# ip_phone_b_miscellaneous.net
KiCad netlist of a schematic drawn in Altium Designer
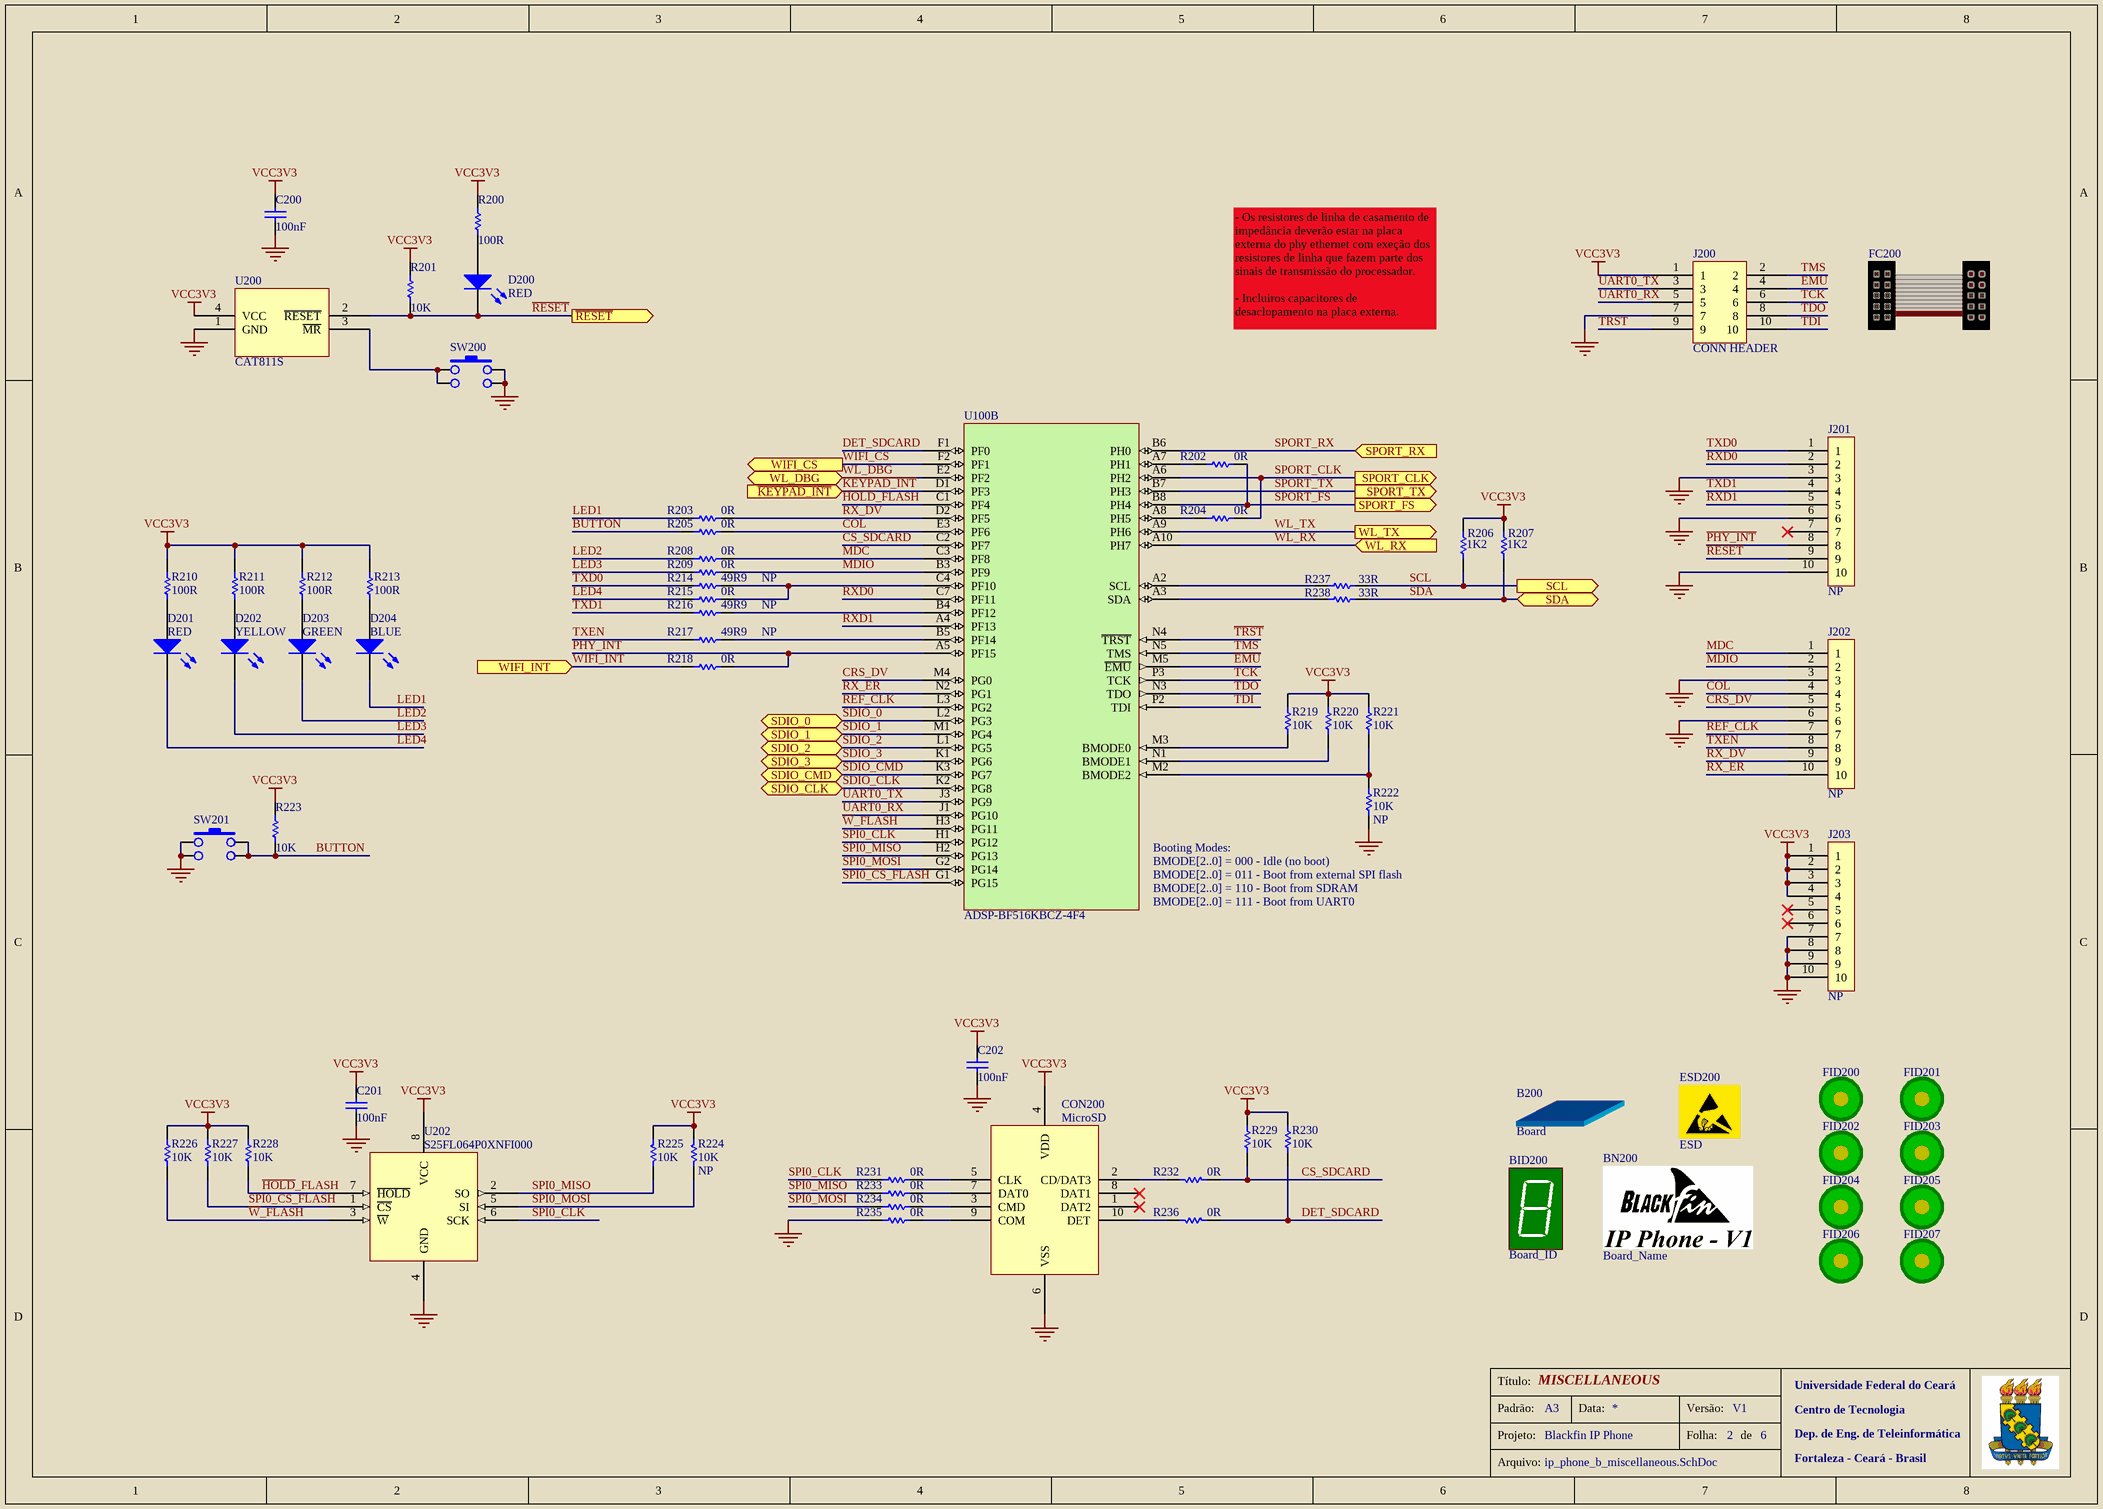
[diagram p0: ip_phone_b_miscellaneous.SchDoc]

(export (version "E")
  (design (tool "Eeschema 10.0.6"))
  (components
    (comp (ref "B200") (value "Board") (libsource (lib "ip_phone") (part "Board")))
    (comp (ref "BID200")
      (value "Board_ID")
      (footprint "ip_phone:BOARD_ID")
      (fields (field (name "EVENDORPART#") "NÃO SE APLICA"))
      (libsource (lib "ip_phone") (part "Board_ID"))
    )
    (comp (ref "BN200")
      (value "Board_Name")
      (footprint "ip_phone:LOGO")
      (fields (field (name "EVENDORPART#") "NÃO SE APLICA"))
      (libsource (lib "ip_phone") (part "Board_Name"))
    )
    (comp (ref "C200")
      (value "100nF")
      (footprint "ip_phone:CC1005-0402")
      (description "MLCC - SMD/SMT 0.1UF 16V 10% 0402")
      (fields (field (name "EVENDORPART#") "810-C1005X7R1C104K") (field (name "MANUFACTURER") "TDK"))
      (libsource (lib "ip_phone") (part "Capacitor"))
    )
    (comp (ref "C201")
      (value "100nF")
      (footprint "ip_phone:CC1005-0402")
      (description "MLCC - SMD/SMT 0.1UF 16V 10% 0402")
      (fields (field (name "EVENDORPART#") "810-C1005X7R1C104K") (field (name "MANUFACTURER") "TDK"))
      (libsource (lib "ip_phone") (part "Capacitor"))
    )
    (comp (ref "C202")
      (value "100nF")
      (footprint "ip_phone:CC1005-0402")
      (description "MLCC - SMD/SMT 0.1UF 16V 10% 0402")
      (fields (field (name "EVENDORPART#") "810-C1005X7R1C104K") (field (name "MANUFACTURER") "TDK"))
      (libsource (lib "ip_phone") (part "Capacitor"))
    )
    (comp (ref "CON200")
      (value "MicroSD")
      (footprint "ip_phone:MICRO_SD")
      (description "CONN MEMORY CARD SD SMD")
      (fields (field (name "MANUFACTURER") "AVX Corporation") (field (name "PART#") "045138008010890+"))
      (libsource (lib "ip_phone") (part "MicroSD"))
    )
    (comp (ref "D200")
      (value "RED")
      (footprint "ip_phone:LED_0603")
      (description "LED")
      (fields (field (name "PART#") "APT1608SURCK") (field (name "MANUFACTURER") "Kingbright"))
      (libsource (lib "ip_phone") (part "LED"))
    )
    (comp (ref "D201")
      (value "RED")
      (footprint "ip_phone:LED_0603")
      (description "LED")
      (fields (field (name "PART#") "APT1608SURCK") (field (name "MANUFACTURER") "Kingbright"))
      (libsource (lib "ip_phone") (part "LED"))
    )
    (comp (ref "D202")
      (value "YELLOW")
      (footprint "ip_phone:LED_0603")
      (description "LED")
      (fields (field (name "PART#") "APT1608SYCK") (field (name "MANUFACTURER") "Kingbright"))
      (libsource (lib "ip_phone") (part "LED"))
    )
    (comp (ref "D203")
      (value "GREEN")
      (footprint "ip_phone:LED_0603")
      (description "LED")
      (fields (field (name "PART#") "APT1608CGCK") (field (name "MANUFACTURER") "Kingbright"))
      (libsource (lib "ip_phone") (part "LED"))
    )
    (comp (ref "D204")
      (value "BLUE")
      (footprint "ip_phone:LED_0603")
      (description "LED")
      (fields (field (name "PART#") "EL-19-21/BHC-AN1P2/3T") (field (name "MANUFACTURER") "Everlight"))
      (libsource (lib "ip_phone") (part "LED"))
    )
    (comp (ref "ESD200")
      (value "ESD")
      (footprint "ip_phone:ESD")
      (fields (field (name "EVENDORPART#") "NÃO SE APLICA"))
      (libsource (lib "ip_phone") (part "ESD"))
    )
    (comp (ref "FC200")
      (value "Flat Cable")
      (fields (field (name "EVENDORPART#") "SAM8218-ND") (field (name "MANUFACTURER") "Samtec"))
      (libsource (lib "ip_phone") (part "Flat_Cable"))
    )
    (comp (ref "FID200")
      (value "Fiducial")
      (footprint "ip_phone:Fiducial")
      (fields (field (name "EVENDORPART#") "NÃO SE APLICA"))
      (libsource (lib "ip_phone") (part "Fiducial"))
    )
    (comp (ref "FID201")
      (value "Fiducial")
      (footprint "ip_phone:Fiducial")
      (fields (field (name "EVENDORPART#") "NÃO SE APLICA"))
      (libsource (lib "ip_phone") (part "Fiducial"))
    )
    (comp (ref "FID202")
      (value "Fiducial")
      (footprint "ip_phone:Fiducial")
      (fields (field (name "EVENDORPART#") "NÃO SE APLICA"))
      (libsource (lib "ip_phone") (part "Fiducial"))
    )
    (comp (ref "FID203")
      (value "Fiducial")
      (footprint "ip_phone:Fiducial")
      (fields (field (name "EVENDORPART#") "NÃO SE APLICA"))
      (libsource (lib "ip_phone") (part "Fiducial"))
    )
    (comp (ref "FID204")
      (value "Fiducial")
      (footprint "ip_phone:Fiducial")
      (fields (field (name "EVENDORPART#") "NÃO SE APLICA"))
      (libsource (lib "ip_phone") (part "Fiducial"))
    )
    (comp (ref "FID205")
      (value "Fiducial")
      (footprint "ip_phone:Fiducial")
      (fields (field (name "EVENDORPART#") "NÃO SE APLICA"))
      (libsource (lib "ip_phone") (part "Fiducial"))
    )
    (comp (ref "FID206")
      (value "Fiducial")
      (footprint "ip_phone:Fiducial")
      (fields (field (name "EVENDORPART#") "NÃO SE APLICA"))
      (libsource (lib "ip_phone") (part "Fiducial"))
    )
    (comp (ref "FID207")
      (value "Fiducial")
      (footprint "ip_phone:Fiducial")
      (fields (field (name "EVENDORPART#") "NÃO SE APLICA"))
      (libsource (lib "ip_phone") (part "Fiducial"))
    )
    (comp (ref "J200")
      (value "CONN HEADER")
      (footprint "ip_phone:CON_JTAG")
      (description "CONN HEADER .050\" 5x2")
      (fields (field (name "EVENDORPART#") "S9012E-05-ND") (field (name "MANUFACTURER") "Sullins"))
      (libsource (lib "ip_phone") (part "Conector JTAG"))
    )
    (comp (ref "J201")
      (value "CONN HEADER")
      (footprint "ip_phone:CONECTOR_10_PIN")
      (description "CONN HEADER .050\" 10POS PCB GOLD")
      (fields
        (field (name "EVENDORPART#") "S9014E-10-ND")
        (field (name "MANUFACTURER") "Sullins Connector Solutions")
        (field (name "NP") "NP")
      )
      (libsource (lib "ip_phone") (part "Conector 10pin"))
    )
    (comp (ref "J202")
      (value "CONN HEADER")
      (footprint "ip_phone:CONECTOR_10_PIN")
      (description "CONN HEADER .050\" 10POS PCB GOLD")
      (fields
        (field (name "EVENDORPART#") "S9014E-10-ND")
        (field (name "MANUFACTURER") "Sullins Connector Solutions")
        (field (name "NP") "NP")
      )
      (libsource (lib "ip_phone") (part "Conector 10pin"))
    )
    (comp (ref "J203")
      (value "CONN HEADER")
      (footprint "ip_phone:CONECTOR_10_PIN")
      (description "CONN HEADER .050\" 10POS PCB GOLD")
      (fields
        (field (name "EVENDORPART#") "S9014E-10-ND")
        (field (name "MANUFACTURER") "Sullins Connector Solutions")
        (field (name "NP") "NP")
      )
      (libsource (lib "ip_phone") (part "Conector 10pin"))
    )
    (comp (ref "R200")
      (value "100R")
      (footprint "ip_phone:CR1608-0603")
      (description "Thick Film Resistors 1/16WATT 100R 0402")
      (fields (field (name "EVENDORPART#") "652-CR0603-JW-101GLF") (field (name "MANUFACTURER") "Bourns"))
      (libsource (lib "ip_phone") (part "Resistor"))
    )
    (comp (ref "R201")
      (value "10K")
      (footprint "ip_phone:CR1005-0402")
      (description "Thick Film Resistors SMD 0402 10K 5%  1/16 W")
      (fields (field (name "EVENDORPART#") "311-10KJRCT-ND") (field (name "MANUFACTURER") "Yageo"))
      (libsource (lib "ip_phone") (part "Resistor"))
    )
    (comp (ref "R202")
      (value "0R")
      (footprint "ip_phone:CR1005-0402")
      (description "Thick Film Resistors 0402 1/16W Jumper")
      (fields
        (field (name "EVENDORPART#") "667-ERJ-2GE0R00X")
        (field (name "MANUFACTURER") "Panasonic Electronic Components")
      )
      (libsource (lib "ip_phone") (part "Resistor"))
    )
    (comp (ref "R203")
      (value "0R")
      (footprint "ip_phone:CR1005-0402")
      (description "Thick Film Resistors 0402 1/16W Jumper")
      (fields
        (field (name "EVENDORPART#") "667-ERJ-2GE0R00X")
        (field (name "MANUFACTURER") "Panasonic Electronic Components")
      )
      (libsource (lib "ip_phone") (part "Resistor"))
    )
    (comp (ref "R204")
      (value "0R")
      (footprint "ip_phone:CR1005-0402")
      (description "Thick Film Resistors 0402 1/16W Jumper")
      (fields
        (field (name "EVENDORPART#") "667-ERJ-2GE0R00X")
        (field (name "MANUFACTURER") "Panasonic Electronic Components")
      )
      (libsource (lib "ip_phone") (part "Resistor"))
    )
    (comp (ref "R205")
      (value "0R")
      (footprint "ip_phone:CR1005-0402")
      (description "Thick Film Resistors 0402 1/16W Jumper")
      (fields
        (field (name "EVENDORPART#") "667-ERJ-2GE0R00X")
        (field (name "MANUFACTURER") "Panasonic Electronic Components")
      )
      (libsource (lib "ip_phone") (part "Resistor"))
    )
    (comp (ref "R206")
      (value "1K2")
      (footprint "ip_phone:CR1005-0402")
      (description "Thick Film Resistors SMD 0402 1K2 5%  1/16 W")
      (fields (field (name "EVENDORPART#") "311-1.2KJRCT-ND") (field (name "MANUFACTURER") "Yageo"))
      (libsource (lib "ip_phone") (part "Resistor"))
    )
    (comp (ref "R207")
      (value "1K2")
      (footprint "ip_phone:CR1005-0402")
      (description "Thick Film Resistors SMD 0402 1K2 5%  1/16 W")
      (fields (field (name "EVENDORPART#") "311-1.2KJRCT-ND") (field (name "MANUFACTURER") "Yageo"))
      (libsource (lib "ip_phone") (part "Resistor"))
    )
    (comp (ref "R208")
      (value "0R")
      (footprint "ip_phone:CR1005-0402")
      (description "Thick Film Resistors 0402 1/16W Jumper")
      (fields
        (field (name "EVENDORPART#") "667-ERJ-2GE0R00X")
        (field (name "MANUFACTURER") "Panasonic Electronic Components")
      )
      (libsource (lib "ip_phone") (part "Resistor"))
    )
    (comp (ref "R209")
      (value "0R")
      (footprint "ip_phone:CR1005-0402")
      (description "Thick Film Resistors 0402 1/16W Jumper")
      (fields
        (field (name "EVENDORPART#") "667-ERJ-2GE0R00X")
        (field (name "MANUFACTURER") "Panasonic Electronic Components")
      )
      (libsource (lib "ip_phone") (part "Resistor"))
    )
    (comp (ref "R210")
      (value "100R")
      (footprint "ip_phone:CR1608-0603")
      (description "Thick Film Resistors 1/16WATT 100R 0402")
      (fields (field (name "EVENDORPART#") "652-CR0603-JW-101GLF") (field (name "MANUFACTURER") "Bourns"))
      (libsource (lib "ip_phone") (part "Resistor"))
    )
    (comp (ref "R211")
      (value "100R")
      (footprint "ip_phone:CR1608-0603")
      (description "Thick Film Resistors 1/16WATT 100R 0402")
      (fields (field (name "EVENDORPART#") "652-CR0603-JW-101GLF") (field (name "MANUFACTURER") "Bourns"))
      (libsource (lib "ip_phone") (part "Resistor"))
    )
    (comp (ref "R212")
      (value "100R")
      (footprint "ip_phone:CR1608-0603")
      (description "Thick Film Resistors 1/16WATT 100R 0402")
      (fields (field (name "EVENDORPART#") "652-CR0603-JW-101GLF") (field (name "MANUFACTURER") "Bourns"))
      (libsource (lib "ip_phone") (part "Resistor"))
    )
    (comp (ref "R213")
      (value "100R")
      (footprint "ip_phone:CR1608-0603")
      (description "Thick Film Resistors 1/16WATT 100R 0402")
      (fields (field (name "EVENDORPART#") "652-CR0603-JW-101GLF") (field (name "MANUFACTURER") "Bourns"))
      (libsource (lib "ip_phone") (part "Resistor"))
    )
    (comp (ref "R214")
      (value "49R9")
      (footprint "ip_phone:CR1005-0402_NP")
      (description "Thick Film Resistors - SMD 1/16watt 49.9ohms 1% 0402")
      (fields
        (field (name "EVENDORPART#") "71-CRCW0402-49.9-E3")
        (field (name "MANUFACTURER") "Vishay/Dale")
        (field (name "NP") "NP")
      )
      (libsource (lib "ip_phone") (part "Resistor"))
    )
    (comp (ref "R215")
      (value "0R")
      (footprint "ip_phone:CR1005-0402")
      (description "Thick Film Resistors 0402 1/16W Jumper")
      (fields
        (field (name "EVENDORPART#") "667-ERJ-2GE0R00X")
        (field (name "MANUFACTURER") "Panasonic Electronic Components")
      )
      (libsource (lib "ip_phone") (part "Resistor"))
    )
    (comp (ref "R216")
      (value "49R9")
      (footprint "ip_phone:CR1005-0402_NP")
      (description "Thick Film Resistors - SMD 1/16watt 49.9ohms 1% 0402")
      (fields
        (field (name "EVENDORPART#") "71-CRCW0402-49.9-E3")
        (field (name "MANUFACTURER") "Vishay/Dale")
        (field (name "NP") "NP")
      )
      (libsource (lib "ip_phone") (part "Resistor"))
    )
    (comp (ref "R217")
      (value "49R9")
      (footprint "ip_phone:CR1005-0402_NP")
      (description "Thick Film Resistors - SMD 1/16watt 49.9ohms 1% 0402")
      (fields
        (field (name "EVENDORPART#") "71-CRCW0402-49.9-E3")
        (field (name "MANUFACTURER") "Vishay/Dale")
        (field (name "NP") "NP")
      )
      (libsource (lib "ip_phone") (part "Resistor"))
    )
    (comp (ref "R218")
      (value "0R")
      (footprint "ip_phone:CR1005-0402")
      (description "Thick Film Resistors 0402 1/16W Jumper")
      (fields
        (field (name "EVENDORPART#") "667-ERJ-2GE0R00X")
        (field (name "MANUFACTURER") "Panasonic Electronic Components")
      )
      (libsource (lib "ip_phone") (part "Resistor"))
    )
    (comp (ref "R219")
      (value "10K")
      (footprint "ip_phone:CR1005-0402")
      (description "Thick Film Resistors SMD 0402 10K 5%  1/16 W")
      (fields (field (name "EVENDORPART#") "311-10KJRCT-ND") (field (name "MANUFACTURER") "Yageo"))
      (libsource (lib "ip_phone") (part "Resistor"))
    )
    (comp (ref "R220")
      (value "10K")
      (footprint "ip_phone:CR1005-0402")
      (description "Thick Film Resistors SMD 0402 10K 5%  1/16 W")
      (fields (field (name "EVENDORPART#") "311-10KJRCT-ND") (field (name "MANUFACTURER") "Yageo"))
      (libsource (lib "ip_phone") (part "Resistor"))
    )
    (comp (ref "R221")
      (value "10K")
      (footprint "ip_phone:CR1005-0402")
      (description "Thick Film Resistors SMD 0402 10K 5%  1/16 W")
      (fields (field (name "EVENDORPART#") "311-10KJRCT-ND") (field (name "MANUFACTURER") "Yageo"))
      (libsource (lib "ip_phone") (part "Resistor"))
    )
    (comp (ref "R222")
      (value "10K")
      (footprint "ip_phone:CR1005-0402_NP")
      (description "Thick Film Resistors SMD 0402 10K 5%  1/16 W")
      (fields
        (field (name "EVENDORPART#") "311-10KJRCT-ND")
        (field (name "MANUFACTURER") "Yageo")
        (field (name "NP") "NP")
      )
      (libsource (lib "ip_phone") (part "Resistor"))
    )
    (comp (ref "R223")
      (value "10K")
      (footprint "ip_phone:CR1005-0402")
      (description "Thick Film Resistors SMD 0402 10K 5%  1/16 W")
      (fields (field (name "EVENDORPART#") "311-10KJRCT-ND") (field (name "MANUFACTURER") "Yageo"))
      (libsource (lib "ip_phone") (part "Resistor"))
    )
    (comp (ref "R224")
      (value "10K")
      (footprint "ip_phone:CR1005-0402_NP")
      (description "Thick Film Resistors SMD 0402 10K 5%  1/16 W")
      (fields
        (field (name "EVENDORPART#") "311-10KJRCT-ND")
        (field (name "MANUFACTURER") "Yageo")
        (field (name "NP") "NP")
      )
      (libsource (lib "ip_phone") (part "Resistor"))
    )
    (comp (ref "R225")
      (value "10K")
      (footprint "ip_phone:CR1005-0402")
      (description "Thick Film Resistors SMD 0402 10K 5%  1/16 W")
      (fields (field (name "EVENDORPART#") "311-10KJRCT-ND") (field (name "MANUFACTURER") "Yageo"))
      (libsource (lib "ip_phone") (part "Resistor"))
    )
    (comp (ref "R226")
      (value "10K")
      (footprint "ip_phone:CR1005-0402")
      (description "Thick Film Resistors SMD 0402 10K 5%  1/16 W")
      (fields (field (name "EVENDORPART#") "311-10KJRCT-ND") (field (name "MANUFACTURER") "Yageo"))
      (libsource (lib "ip_phone") (part "Resistor"))
    )
    (comp (ref "R227")
      (value "10K")
      (footprint "ip_phone:CR1005-0402")
      (description "Thick Film Resistors SMD 0402 10K 5%  1/16 W")
      (fields (field (name "EVENDORPART#") "311-10KJRCT-ND") (field (name "MANUFACTURER") "Yageo"))
      (libsource (lib "ip_phone") (part "Resistor"))
    )
    (comp (ref "R228")
      (value "10K")
      (footprint "ip_phone:CR1005-0402")
      (description "Thick Film Resistors SMD 0402 10K 5%  1/16 W")
      (fields (field (name "EVENDORPART#") "311-10KJRCT-ND") (field (name "MANUFACTURER") "Yageo"))
      (libsource (lib "ip_phone") (part "Resistor"))
    )
    (comp (ref "R229")
      (value "10K")
      (footprint "ip_phone:CR1005-0402")
      (description "Thick Film Resistors SMD 0402 10K 5%  1/16 W")
      (fields (field (name "EVENDORPART#") "311-10KJRCT-ND") (field (name "MANUFACTURER") "Yageo"))
      (libsource (lib "ip_phone") (part "Resistor"))
    )
    (comp (ref "R230")
      (value "10K")
      (footprint "ip_phone:CR1005-0402")
      (description "Thick Film Resistors SMD 0402 10K 5%  1/16 W")
      (fields (field (name "EVENDORPART#") "311-10KJRCT-ND") (field (name "MANUFACTURER") "Yageo"))
      (libsource (lib "ip_phone") (part "Resistor"))
    )
    (comp (ref "R231")
      (value "0R")
      (footprint "ip_phone:CR1005-0402")
      (description "Thick Film Resistors 0402 1/16W Jumper")
      (fields
        (field (name "EVENDORPART#") "667-ERJ-2GE0R00X")
        (field (name "MANUFACTURER") "Panasonic Electronic Components")
      )
      (libsource (lib "ip_phone") (part "Resistor"))
    )
    (comp (ref "R232")
      (value "0R")
      (footprint "ip_phone:CR1005-0402")
      (description "Thick Film Resistors 0402 1/16W Jumper")
      (fields
        (field (name "EVENDORPART#") "667-ERJ-2GE0R00X")
        (field (name "MANUFACTURER") "Panasonic Electronic Components")
      )
      (libsource (lib "ip_phone") (part "Resistor"))
    )
    (comp (ref "R233")
      (value "0R")
      (footprint "ip_phone:CR1005-0402")
      (description "Thick Film Resistors 0402 1/16W Jumper")
      (fields
        (field (name "EVENDORPART#") "667-ERJ-2GE0R00X")
        (field (name "MANUFACTURER") "Panasonic Electronic Components")
      )
      (libsource (lib "ip_phone") (part "Resistor"))
    )
    (comp (ref "R234")
      (value "0R")
      (footprint "ip_phone:CR1005-0402")
      (description "Thick Film Resistors 0402 1/16W Jumper")
      (fields
        (field (name "EVENDORPART#") "667-ERJ-2GE0R00X")
        (field (name "MANUFACTURER") "Panasonic Electronic Components")
      )
      (libsource (lib "ip_phone") (part "Resistor"))
    )
    (comp (ref "R235")
      (value "0R")
      (footprint "ip_phone:CR1005-0402")
      (description "Thick Film Resistors 0402 1/16W Jumper")
      (fields
        (field (name "EVENDORPART#") "667-ERJ-2GE0R00X")
        (field (name "MANUFACTURER") "Panasonic Electronic Components")
      )
      (libsource (lib "ip_phone") (part "Resistor"))
    )
    (comp (ref "R236")
      (value "0R")
      (footprint "ip_phone:CR1005-0402")
      (description "Thick Film Resistors 0402 1/16W Jumper")
      (fields
        (field (name "EVENDORPART#") "667-ERJ-2GE0R00X")
        (field (name "MANUFACTURER") "Panasonic Electronic Components")
      )
      (libsource (lib "ip_phone") (part "Resistor"))
    )
    (comp (ref "R237")
      (value "33R")
      (footprint "ip_phone:CR1005-0402")
      (description "Thick Film Resistors SMD 0402 33R 5%  1/16 W")
      (fields (field (name "EVENDORPART#") "311-33JRCT-ND") (field (name "MANUFACTURER") "Yageo"))
      (libsource (lib "ip_phone") (part "Resistor"))
    )
    (comp (ref "R238")
      (value "33R")
      (footprint "ip_phone:CR1005-0402")
      (description "Thick Film Resistors SMD 0402 33R 5%  1/16 W")
      (fields (field (name "EVENDORPART#") "311-33JRCT-ND") (field (name "MANUFACTURER") "Yageo"))
      (libsource (lib "ip_phone") (part "Resistor"))
    )
    (comp (ref "SW200")
      (value "SW")
      (footprint "ip_phone:PUSH-PTS525")
      (description "Switch tact, SMT, SPST, 160gf, 5.25 mm L x 5.25 mm W x 1.5 mm H")
      (fields (field (name "MANUFACTURER") "C&K Components") (field (name "PART#") "PTS525SM10SMTR LFS"))
      (libsource (lib "ip_phone") (part "SWITCH_PUSH_NA_SMD"))
    )
    (comp (ref "SW201")
      (value "SW")
      (footprint "ip_phone:PUSH-PTS525")
      (description "Switch tact, SMT, SPST, 160gf, 5.25 mm L x 5.25 mm W x 1.5 mm H")
      (fields (field (name "MANUFACTURER") "C&K Components") (field (name "PART#") "PTS525SM10SMTR LFS"))
      (libsource (lib "ip_phone") (part "SWITCH_PUSH_NA_SMD"))
    )
    (comp (ref "U100")
      (value "ADSP-BF516KBCZ-4F4")
      (footprint "ip_phone:BGA168")
      (description "Low Power Blackfin with Advanced Embedded Connectivity")
      (fields (field (name "MANUFACTURER") "Analog Device"))
      (libsource (lib "ip_phone") (part "ADSP-BF516KBCZ-4F4"))
    )
    (comp (ref "U200")
      (value "CAT811S")
      (footprint "ip_phone:SOT-143")
      (description "IC Supervisor MPU 2.93V  SOT-143")
      (fields (field (name "PART#") "CAT811STBI-GT3") (field (name "MANUFACTURER") "ON Semiconductor"))
      (libsource (lib "ip_phone") (part "CAT811S"))
    )
    (comp (ref "U202")
      (value "S25FL064P0XNFI000")
      (footprint "ip_phone:WSON8")
      (description "Flash Mem Serial-SPI 3V/3.3V 64M-Bit 64M x 1 8ns 8-Pin WSON Tray")
      (fields (field (name "MANUFACTURER") "Spansion"))
      (libsource (lib "ip_phone") (part "S25FL064P0XNFI000"))
    )
  )
  (nets
    (net (code "1") (name "/BUTTON") (class "Default")
      (node (ref "R205") (pin "1") (pinfunction "1_1") (pintype "passive"))
      (node (ref "R223") (pin "1") (pinfunction "1_1") (pintype "passive"))
      (node (ref "SW201") (pin "3") (pinfunction "3_3") (pintype "passive"))
      (node (ref "SW201") (pin "4") (pinfunction "4_4") (pintype "passive"))
    )
    (net (code "2") (name "/COL") (class "Default")
      (node (ref "J202") (pin "4") (pinfunction "4_4") (pintype "passive"))
      (node (ref "R205") (pin "2") (pinfunction "2_2") (pintype "passive"))
      (node (ref "U100") (pin "E3") (pinfunction "PF6_E3") (pintype "bidirectional"))
    )
    (net (code "3") (name "/CRS_DV") (class "Default")
      (node (ref "J202") (pin "5") (pinfunction "5_5") (pintype "passive"))
      (node (ref "U100") (pin "M4") (pinfunction "PG0_M4") (pintype "bidirectional"))
    )
    (net (code "4") (name "/CS_SDCARD") (class "Default")
      (node (ref "R229") (pin "1") (pinfunction "1_1") (pintype "passive"))
      (node (ref "R232") (pin "1") (pinfunction "1_1") (pintype "passive"))
      (node (ref "U100") (pin "C2") (pinfunction "PF7_C2") (pintype "bidirectional"))
    )
    (net (code "5") (name "/DET_SDCARD") (class "Default")
      (node (ref "R230") (pin "1") (pinfunction "1_1") (pintype "passive"))
      (node (ref "R236") (pin "1") (pinfunction "1_1") (pintype "passive"))
      (node (ref "U100") (pin "F1") (pinfunction "PF0_F1") (pintype "bidirectional"))
    )
    (net (code "6") (name "/LED1") (class "Default")
      (node (ref "D204") (pin "2") (pinfunction "K_2") (pintype "passive"))
      (node (ref "R203") (pin "1") (pinfunction "1_1") (pintype "passive"))
    )
    (net (code "7") (name "/LED2") (class "Default")
      (node (ref "D203") (pin "2") (pinfunction "K_2") (pintype "passive"))
      (node (ref "R208") (pin "1") (pinfunction "1_1") (pintype "passive"))
    )
    (net (code "8") (name "/LED3") (class "Default")
      (node (ref "D202") (pin "2") (pinfunction "K_2") (pintype "passive"))
      (node (ref "R209") (pin "1") (pinfunction "1_1") (pintype "passive"))
    )
    (net (code "9") (name "/LED4") (class "Default")
      (node (ref "D201") (pin "2") (pinfunction "K_2") (pintype "passive"))
      (node (ref "R215") (pin "1") (pinfunction "1_1") (pintype "passive"))
    )
    (net (code "10") (name "/MDC") (class "Default")
      (node (ref "J202") (pin "1") (pinfunction "1_1") (pintype "passive"))
      (node (ref "R208") (pin "2") (pinfunction "2_2") (pintype "passive"))
      (node (ref "U100") (pin "C3") (pinfunction "PF8_C3") (pintype "bidirectional"))
    )
    (net (code "11") (name "/MDIO") (class "Default")
      (node (ref "J202") (pin "2") (pinfunction "2_2") (pintype "passive"))
      (node (ref "R209") (pin "2") (pinfunction "2_2") (pintype "passive"))
      (node (ref "U100") (pin "B3") (pinfunction "PF9_B3") (pintype "bidirectional"))
    )
    (net (code "12") (name "/REF_CLK") (class "Default")
      (node (ref "J202") (pin "7") (pinfunction "7_7") (pintype "passive"))
      (node (ref "U100") (pin "L3") (pinfunction "PG2_L3") (pintype "bidirectional"))
    )
    (net (code "13") (name "/RXD0") (class "Default")
      (node (ref "J201") (pin "2") (pinfunction "2_2") (pintype "passive"))
      (node (ref "U100") (pin "C7") (pinfunction "PF11_C7") (pintype "bidirectional"))
    )
    (net (code "14") (name "/RXD1") (class "Default")
      (node (ref "J201") (pin "5") (pinfunction "5_5") (pintype "passive"))
      (node (ref "U100") (pin "A4") (pinfunction "PF13_A4") (pintype "bidirectional"))
    )
    (net (code "15") (name "/RX_DV") (class "Default")
      (node (ref "J202") (pin "9") (pinfunction "9_9") (pintype "passive"))
      (node (ref "R203") (pin "2") (pinfunction "2_2") (pintype "passive"))
      (node (ref "U100") (pin "D2") (pinfunction "PF5_D2") (pintype "bidirectional"))
    )
    (net (code "16") (name "/RX_ER") (class "Default")
      (node (ref "J202") (pin "10") (pinfunction "10_10") (pintype "passive"))
      (node (ref "U100") (pin "N2") (pinfunction "PG1_N2") (pintype "bidirectional"))
    )
    (net (code "17") (name "/SCL") (class "Default")
      (node (ref "R206") (pin "2") (pinfunction "2_2") (pintype "passive"))
      (node (ref "R237") (pin "2") (pinfunction "2_2") (pintype "passive"))
    )
    (net (code "18") (name "/SDA") (class "Default")
      (node (ref "R207") (pin "2") (pinfunction "2_2") (pintype "passive"))
      (node (ref "R238") (pin "2") (pinfunction "2_2") (pintype "passive"))
    )
    (net (code "19") (name "/SDIO_0") (class "Default")
      (node (ref "U100") (pin "L2") (pinfunction "PG3_L2") (pintype "bidirectional"))
    )
    (net (code "20") (name "/SDIO_1") (class "Default")
      (node (ref "U100") (pin "M1") (pinfunction "PG4_M1") (pintype "bidirectional"))
    )
    (net (code "21") (name "/SDIO_2") (class "Default")
      (node (ref "U100") (pin "L1") (pinfunction "PG5_L1") (pintype "bidirectional"))
    )
    (net (code "22") (name "/SDIO_3") (class "Default")
      (node (ref "U100") (pin "K1") (pinfunction "PG6_K1") (pintype "bidirectional"))
    )
    (net (code "23") (name "/SDIO_CLK") (class "Default")
      (node (ref "U100") (pin "K2") (pinfunction "PG8_K2") (pintype "bidirectional"))
    )
    (net (code "24") (name "/SDIO_CMD") (class "Default")
      (node (ref "U100") (pin "K3") (pinfunction "PG7_K3") (pintype "bidirectional"))
    )
    (net (code "25") (name "/SPI0_CLK") (class "Default")
      (node (ref "R231") (pin "1") (pinfunction "1_1") (pintype "passive"))
      (node (ref "U100") (pin "H1") (pinfunction "PG12_H1") (pintype "bidirectional"))
      (node (ref "U202") (pin "6") (pinfunction "SCK_6") (pintype "input"))
    )
    (net (code "26") (name "/SPI0_MISO") (class "Default")
      (node (ref "R225") (pin "1") (pinfunction "1_1") (pintype "passive"))
      (node (ref "R233") (pin "1") (pinfunction "1_1") (pintype "passive"))
      (node (ref "U100") (pin "H2") (pinfunction "PG13_H2") (pintype "bidirectional"))
      (node (ref "U202") (pin "2") (pinfunction "SO_2") (pintype "output"))
    )
    (net (code "27") (name "/SPI0_MOSI") (class "Default")
      (node (ref "R224") (pin "1") (pinfunction "1_1") (pintype "passive"))
      (node (ref "R234") (pin "1") (pinfunction "1_1") (pintype "passive"))
      (node (ref "U100") (pin "G2") (pinfunction "PG14_G2") (pintype "bidirectional"))
      (node (ref "U202") (pin "5") (pinfunction "SI_5") (pintype "input"))
    )
    (net (code "28") (name "/SPI0~{_CS}_FLASH") (class "Default")
      (node (ref "R227") (pin "1") (pinfunction "1_1") (pintype "passive"))
      (node (ref "U100") (pin "G1") (pinfunction "PG15_G1") (pintype "bidirectional"))
      (node (ref "U202") (pin "1") (pinfunction "~{CS}_1") (pintype "input"))
    )
    (net (code "29") (name "/SPORT_CLK") (class "Default")
      (node (ref "R204") (pin "2") (pinfunction "2_2") (pintype "passive"))
      (node (ref "U100") (pin "A6") (pinfunction "PH2_A6") (pintype "bidirectional"))
    )
    (net (code "30") (name "/SPORT_FS") (class "Default")
      (node (ref "R202") (pin "2") (pinfunction "2_2") (pintype "passive"))
      (node (ref "U100") (pin "B8") (pinfunction "PH4_B8") (pintype "bidirectional"))
    )
    (net (code "31") (name "/SPORT_RX") (class "Default")
      (node (ref "U100") (pin "B6") (pinfunction "PH0_B6") (pintype "bidirectional"))
    )
    (net (code "32") (name "/SPORT_TX") (class "Default")
      (node (ref "U100") (pin "B7") (pinfunction "PH3_B7") (pintype "bidirectional"))
    )
    (net (code "33") (name "/TCK") (class "Default")
      (node (ref "J200") (pin "6") (pinfunction "6_6") (pintype "passive"))
      (node (ref "U100") (pin "P3") (pinfunction "TCK_P3") (pintype "output"))
    )
    (net (code "34") (name "/TDI") (class "Default")
      (node (ref "J200") (pin "10") (pinfunction "10_10") (pintype "passive"))
      (node (ref "U100") (pin "P2") (pinfunction "TDI_P2") (pintype "input"))
    )
    (net (code "35") (name "/TDO") (class "Default")
      (node (ref "J200") (pin "8") (pinfunction "8_8") (pintype "passive"))
      (node (ref "U100") (pin "N3") (pinfunction "TDO_N3") (pintype "output"))
    )
    (net (code "36") (name "/TMS") (class "Default")
      (node (ref "J200") (pin "2") (pinfunction "2_2") (pintype "passive"))
      (node (ref "U100") (pin "N5") (pinfunction "TMS_N5") (pintype "input"))
    )
    (net (code "37") (name "/TXD0") (class "Default")
      (node (ref "J201") (pin "1") (pinfunction "1_1") (pintype "passive"))
      (node (ref "R214") (pin "1") (pinfunction "1_1") (pintype "passive"))
    )
    (net (code "38") (name "/TXD1") (class "Default")
      (node (ref "J201") (pin "4") (pinfunction "4_4") (pintype "passive"))
      (node (ref "R216") (pin "1") (pinfunction "1_1") (pintype "passive"))
    )
    (net (code "39") (name "/TXEN") (class "Default")
      (node (ref "J202") (pin "8") (pinfunction "8_8") (pintype "passive"))
      (node (ref "R217") (pin "1") (pinfunction "1_1") (pintype "passive"))
    )
    (net (code "40") (name "/UART0_RX") (class "Default")
      (node (ref "J200") (pin "5") (pinfunction "5_5") (pintype "passive"))
      (node (ref "U100") (pin "J1") (pinfunction "PG10_J1") (pintype "bidirectional"))
    )
    (net (code "41") (name "/UART0_TX") (class "Default")
      (node (ref "J200") (pin "3") (pinfunction "3_3") (pintype "passive"))
      (node (ref "U100") (pin "J3") (pinfunction "PG9_J3") (pintype "bidirectional"))
    )
    (net (code "42") (name "/WIFI_CS") (class "Default")
      (node (ref "U100") (pin "F2") (pinfunction "PF1_F2") (pintype "bidirectional"))
    )
    (net (code "43") (name "/WIFI_INT") (class "Default")
      (node (ref "R218") (pin "1") (pinfunction "1_1") (pintype "passive"))
    )
    (net (code "44") (name "/WL_DBG") (class "Default")
      (node (ref "U100") (pin "E2") (pinfunction "PF2_E2") (pintype "bidirectional"))
    )
    (net (code "45") (name "/WL_RX") (class "Default")
      (node (ref "U100") (pin "A10") (pinfunction "PH7_A10") (pintype "bidirectional"))
    )
    (net (code "46") (name "/WL_TX") (class "Default")
      (node (ref "U100") (pin "A9") (pinfunction "PH6_A9") (pintype "bidirectional"))
    )
    (net (code "47") (name "/~{EMU}") (class "Default")
      (node (ref "J200") (pin "4") (pinfunction "4_4") (pintype "passive"))
      (node (ref "U100") (pin "M5") (pinfunction "~{EMU}_M5") (pintype "output"))
    )
    (net (code "48") (name "/~{HOLD}_FLASH") (class "Default")
      (node (ref "R228") (pin "1") (pinfunction "1_1") (pintype "passive"))
      (node (ref "U100") (pin "C1") (pinfunction "PF4_C1") (pintype "bidirectional"))
      (node (ref "U202") (pin "7") (pinfunction "~{HOLD}_7") (pintype "input"))
    )
    (net (code "49") (name "/~{KEYPAD_INT}") (class "Default")
      (node (ref "U100") (pin "D1") (pinfunction "PF3_D1") (pintype "bidirectional"))
    )
    (net (code "50") (name "/~{PHY_INT}") (class "Default")
      (node (ref "J201") (pin "8") (pinfunction "8_8") (pintype "passive"))
      (node (ref "R218") (pin "2") (pinfunction "2_2") (pintype "passive"))
      (node (ref "U100") (pin "A5") (pinfunction "PF15_A5") (pintype "bidirectional"))
    )
    (net (code "51") (name "/~{RESET}") (class "Default")
      (node (ref "D200") (pin "2") (pinfunction "K_2") (pintype "passive"))
      (node (ref "J201") (pin "9") (pinfunction "9_9") (pintype "passive"))
      (node (ref "R201") (pin "1") (pinfunction "1_1") (pintype "passive"))
      (node (ref "U200") (pin "2") (pinfunction "~{RESET}_2") (pintype "passive"))
    )
    (net (code "52") (name "/~{TRST}") (class "Default")
      (node (ref "J200") (pin "9") (pinfunction "9_9") (pintype "passive"))
      (node (ref "U100") (pin "N4") (pinfunction "~{TRST}_N4") (pintype "input"))
    )
    (net (code "53") (name "/~{W}_FLASH") (class "Default")
      (node (ref "R226") (pin "1") (pinfunction "1_1") (pintype "passive"))
      (node (ref "U100") (pin "H3") (pinfunction "PG11_H3") (pintype "bidirectional"))
      (node (ref "U202") (pin "3") (pinfunction "~{W}_3") (pintype "input"))
    )
    (net (code "54") (name "GND") (class "Default")
      (node (ref "C200") (pin "1") (pinfunction "1_1") (pintype "passive"))
      (node (ref "C201") (pin "1") (pinfunction "1_1") (pintype "passive"))
      (node (ref "C202") (pin "1") (pinfunction "1_1") (pintype "passive"))
      (node (ref "CON200") (pin "6") (pinfunction "VSS_6") (pintype "passive"))
      (node (ref "J200") (pin "7") (pinfunction "7_7") (pintype "passive"))
      (node (ref "J201") (pin "10") (pinfunction "10_10") (pintype "passive"))
      (node (ref "J201") (pin "3") (pinfunction "3_3") (pintype "passive"))
      (node (ref "J201") (pin "6") (pinfunction "6_6") (pintype "passive"))
      (node (ref "J202") (pin "3") (pinfunction "3_3") (pintype "passive"))
      (node (ref "J202") (pin "6") (pinfunction "6_6") (pintype "passive"))
      (node (ref "J203") (pin "10") (pinfunction "10_10") (pintype "passive"))
      (node (ref "J203") (pin "7") (pinfunction "7_7") (pintype "passive"))
      (node (ref "J203") (pin "8") (pinfunction "8_8") (pintype "passive"))
      (node (ref "J203") (pin "9") (pinfunction "9_9") (pintype "passive"))
      (node (ref "R222") (pin "1") (pinfunction "1_1") (pintype "passive"))
      (node (ref "R235") (pin "1") (pinfunction "1_1") (pintype "passive"))
      (node (ref "SW200") (pin "1") (pinfunction "1_1") (pintype "passive"))
      (node (ref "SW200") (pin "2") (pinfunction "2_2") (pintype "passive"))
      (node (ref "SW201") (pin "1") (pinfunction "1_1") (pintype "passive"))
      (node (ref "SW201") (pin "2") (pinfunction "2_2") (pintype "passive"))
      (node (ref "U200") (pin "1") (pinfunction "GND_1") (pintype "passive"))
      (node (ref "U202") (pin "4") (pinfunction "GND_4") (pintype "power_in"))
    )
    (net (code "55") (name "Net-(CON200-CD{slash}DAT3)") (class "Default")
      (node (ref "CON200") (pin "2") (pinfunction "CD/DAT3_2") (pintype "passive"))
      (node (ref "R232") (pin "2") (pinfunction "2_2") (pintype "passive"))
    )
    (net (code "56") (name "Net-(CON200-CLK)") (class "Default")
      (node (ref "CON200") (pin "5") (pinfunction "CLK_5") (pintype "passive"))
      (node (ref "R231") (pin "2") (pinfunction "2_2") (pintype "passive"))
    )
    (net (code "57") (name "Net-(CON200-CMD)") (class "Default")
      (node (ref "CON200") (pin "3") (pinfunction "CMD_3") (pintype "passive"))
      (node (ref "R234") (pin "2") (pinfunction "2_2") (pintype "passive"))
    )
    (net (code "58") (name "Net-(CON200-COM)") (class "Default")
      (node (ref "CON200") (pin "9") (pinfunction "COM_9") (pintype "passive"))
      (node (ref "R235") (pin "2") (pinfunction "2_2") (pintype "passive"))
    )
    (net (code "59") (name "Net-(CON200-DAT0)") (class "Default")
      (node (ref "CON200") (pin "7") (pinfunction "DAT0_7") (pintype "passive"))
      (node (ref "R233") (pin "2") (pinfunction "2_2") (pintype "passive"))
    )
    (net (code "60") (name "Net-(CON200-DET)") (class "Default")
      (node (ref "CON200") (pin "10") (pinfunction "DET_10") (pintype "passive"))
      (node (ref "R236") (pin "2") (pinfunction "2_2") (pintype "passive"))
    )
    (net (code "61") (name "Net-(D200-A)") (class "Default")
      (node (ref "D200") (pin "1") (pinfunction "A_1") (pintype "passive"))
      (node (ref "R200") (pin "1") (pinfunction "1_1") (pintype "passive"))
    )
    (net (code "62") (name "Net-(D201-A)") (class "Default")
      (node (ref "D201") (pin "1") (pinfunction "A_1") (pintype "passive"))
      (node (ref "R210") (pin "1") (pinfunction "1_1") (pintype "passive"))
    )
    (net (code "63") (name "Net-(D202-A)") (class "Default")
      (node (ref "D202") (pin "1") (pinfunction "A_1") (pintype "passive"))
      (node (ref "R211") (pin "1") (pinfunction "1_1") (pintype "passive"))
    )
    (net (code "64") (name "Net-(D203-A)") (class "Default")
      (node (ref "D203") (pin "1") (pinfunction "A_1") (pintype "passive"))
      (node (ref "R212") (pin "1") (pinfunction "1_1") (pintype "passive"))
    )
    (net (code "65") (name "Net-(D204-A)") (class "Default")
      (node (ref "D204") (pin "1") (pinfunction "A_1") (pintype "passive"))
      (node (ref "R213") (pin "1") (pinfunction "1_1") (pintype "passive"))
    )
    (net (code "66") (name "Net-(U100B-BMODE0)") (class "Default")
      (node (ref "R219") (pin "1") (pinfunction "1_1") (pintype "passive"))
      (node (ref "U100") (pin "M3") (pinfunction "BMODE0_M3") (pintype "input"))
    )
    (net (code "67") (name "Net-(U100B-BMODE1)") (class "Default")
      (node (ref "R220") (pin "1") (pinfunction "1_1") (pintype "passive"))
      (node (ref "U100") (pin "N1") (pinfunction "BMODE1_N1") (pintype "input"))
    )
    (net (code "68") (name "Net-(U100B-BMODE2)") (class "Default")
      (node (ref "R221") (pin "1") (pinfunction "1_1") (pintype "passive"))
      (node (ref "R222") (pin "2") (pinfunction "2_2") (pintype "passive"))
      (node (ref "U100") (pin "M2") (pinfunction "BMODE2_M2") (pintype "input"))
    )
    (net (code "69") (name "Net-(U100B-PF10)") (class "Default")
      (node (ref "R214") (pin "2") (pinfunction "2_2") (pintype "passive"))
      (node (ref "R215") (pin "2") (pinfunction "2_2") (pintype "passive"))
      (node (ref "U100") (pin "C4") (pinfunction "PF10_C4") (pintype "bidirectional"))
    )
    (net (code "70") (name "Net-(U100B-PF12)") (class "Default")
      (node (ref "R216") (pin "2") (pinfunction "2_2") (pintype "passive"))
      (node (ref "U100") (pin "B4") (pinfunction "PF12_B4") (pintype "bidirectional"))
    )
    (net (code "71") (name "Net-(U100B-PF14)") (class "Default")
      (node (ref "R217") (pin "2") (pinfunction "2_2") (pintype "passive"))
      (node (ref "U100") (pin "B5") (pinfunction "PF14_B5") (pintype "bidirectional"))
    )
    (net (code "72") (name "Net-(U100B-PH1)") (class "Default")
      (node (ref "R202") (pin "1") (pinfunction "1_1") (pintype "passive"))
      (node (ref "U100") (pin "A7") (pinfunction "PH1_A7") (pintype "bidirectional"))
    )
    (net (code "73") (name "Net-(U100B-PH5)") (class "Default")
      (node (ref "R204") (pin "1") (pinfunction "1_1") (pintype "passive"))
      (node (ref "U100") (pin "A8") (pinfunction "PH5_A8") (pintype "bidirectional"))
    )
    (net (code "74") (name "Net-(U100B-SCL)") (class "Default")
      (node (ref "R237") (pin "1") (pinfunction "1_1") (pintype "passive"))
      (node (ref "U100") (pin "A2") (pinfunction "SCL_A2") (pintype "bidirectional"))
    )
    (net (code "75") (name "Net-(U100B-SDA)") (class "Default")
      (node (ref "R238") (pin "1") (pinfunction "1_1") (pintype "passive"))
      (node (ref "U100") (pin "A3") (pinfunction "SDA_A3") (pintype "bidirectional"))
    )
    (net (code "76") (name "Net-(U200-~{MR})") (class "Default")
      (node (ref "SW200") (pin "3") (pinfunction "3_3") (pintype "passive"))
      (node (ref "SW200") (pin "4") (pinfunction "4_4") (pintype "passive"))
      (node (ref "U200") (pin "3") (pinfunction "~{MR}_3") (pintype "passive"))
    )
    (net (code "77") (name "VCC3V3") (class "Default")
      (node (ref "C200") (pin "2") (pinfunction "2_2") (pintype "passive"))
      (node (ref "C201") (pin "2") (pinfunction "2_2") (pintype "passive"))
      (node (ref "C202") (pin "2") (pinfunction "2_2") (pintype "passive"))
      (node (ref "CON200") (pin "4") (pinfunction "VDD_4") (pintype "passive"))
      (node (ref "J200") (pin "1") (pinfunction "1_1") (pintype "passive"))
      (node (ref "J203") (pin "1") (pinfunction "1_1") (pintype "passive"))
      (node (ref "J203") (pin "2") (pinfunction "2_2") (pintype "passive"))
      (node (ref "J203") (pin "3") (pinfunction "3_3") (pintype "passive"))
      (node (ref "J203") (pin "4") (pinfunction "4_4") (pintype "passive"))
      (node (ref "R200") (pin "2") (pinfunction "2_2") (pintype "passive"))
      (node (ref "R201") (pin "2") (pinfunction "2_2") (pintype "passive"))
      (node (ref "R206") (pin "1") (pinfunction "1_1") (pintype "passive"))
      (node (ref "R207") (pin "1") (pinfunction "1_1") (pintype "passive"))
      (node (ref "R210") (pin "2") (pinfunction "2_2") (pintype "passive"))
      (node (ref "R211") (pin "2") (pinfunction "2_2") (pintype "passive"))
      (node (ref "R212") (pin "2") (pinfunction "2_2") (pintype "passive"))
      (node (ref "R213") (pin "2") (pinfunction "2_2") (pintype "passive"))
      (node (ref "R219") (pin "2") (pinfunction "2_2") (pintype "passive"))
      (node (ref "R220") (pin "2") (pinfunction "2_2") (pintype "passive"))
      (node (ref "R221") (pin "2") (pinfunction "2_2") (pintype "passive"))
      (node (ref "R223") (pin "2") (pinfunction "2_2") (pintype "passive"))
      (node (ref "R224") (pin "2") (pinfunction "2_2") (pintype "passive"))
      (node (ref "R225") (pin "2") (pinfunction "2_2") (pintype "passive"))
      (node (ref "R226") (pin "2") (pinfunction "2_2") (pintype "passive"))
      (node (ref "R227") (pin "2") (pinfunction "2_2") (pintype "passive"))
      (node (ref "R228") (pin "2") (pinfunction "2_2") (pintype "passive"))
      (node (ref "R229") (pin "2") (pinfunction "2_2") (pintype "passive"))
      (node (ref "R230") (pin "2") (pinfunction "2_2") (pintype "passive"))
      (node (ref "U200") (pin "4") (pinfunction "VCC_4") (pintype "passive"))
      (node (ref "U202") (pin "8") (pinfunction "VCC_8") (pintype "power_in"))
    )
    (net (code "78") (name "unconnected-(CON200-DAT1-Pad8)") (class "Default")
      (node (ref "CON200") (pin "8") (pinfunction "DAT1_8") (pintype "passive+no_connect"))
    )
    (net (code "79") (name "unconnected-(CON200-DAT2-Pad1)") (class "Default")
      (node (ref "CON200") (pin "1") (pinfunction "DAT2_1") (pintype "passive+no_connect"))
    )
    (net (code "80") (name "unconnected-(J201-Pad7)") (class "Default")
      (node (ref "J201") (pin "7") (pinfunction "7_7") (pintype "passive+no_connect"))
    )
    (net (code "81") (name "unconnected-(J203-Pad5)") (class "Default")
      (node (ref "J203") (pin "5") (pinfunction "5_5") (pintype "passive+no_connect"))
    )
    (net (code "82") (name "unconnected-(J203-Pad6)") (class "Default")
      (node (ref "J203") (pin "6") (pinfunction "6_6") (pintype "passive+no_connect"))
    )
  )
)
